# 20W-IR-Blaster_Simplified.net
KiCad netlist of a schematic drawn in EAGLE
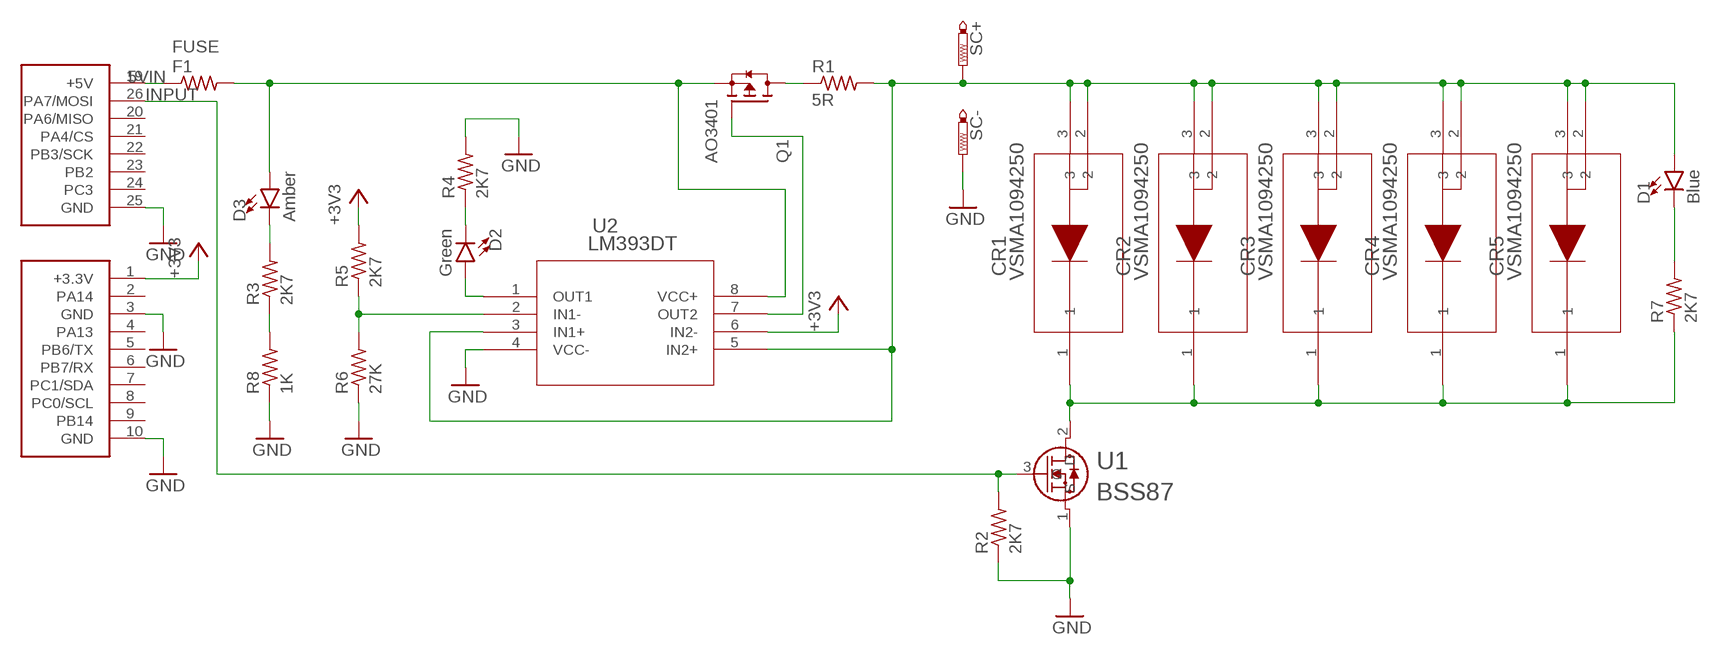
[diagram p0: schematic, sheet 1]

(export (version "E")
  (design (tool "Eeschema 10.0.6"))
  (components
    (comp (ref "CR1")
      (value "VSMA1094250")
      (footprint "eagle-import:DIODE_VSMA1094250_VIS")
      (fields (field (name "COPYRIGHT") "Copyright (C) 2025 Ultra Librarian. All rights reserved."))
      (libsource (lib "eagle-import") (part "VSMA1094250"))
    )
    (comp (ref "CR2")
      (value "VSMA1094250")
      (footprint "eagle-import:DIODE_VSMA1094250_VIS")
      (fields (field (name "COPYRIGHT") "Copyright (C) 2025 Ultra Librarian. All rights reserved."))
      (libsource (lib "eagle-import") (part "VSMA1094250"))
    )
    (comp (ref "CR3")
      (value "VSMA1094250")
      (footprint "eagle-import:DIODE_VSMA1094250_VIS")
      (fields (field (name "COPYRIGHT") "Copyright (C) 2025 Ultra Librarian. All rights reserved."))
      (libsource (lib "eagle-import") (part "VSMA1094250"))
    )
    (comp (ref "CR4")
      (value "VSMA1094250")
      (footprint "eagle-import:DIODE_VSMA1094250_VIS")
      (fields (field (name "COPYRIGHT") "Copyright (C) 2025 Ultra Librarian. All rights reserved."))
      (libsource (lib "eagle-import") (part "VSMA1094250"))
    )
    (comp (ref "CR5")
      (value "VSMA1094250")
      (footprint "eagle-import:DIODE_VSMA1094250_VIS")
      (fields (field (name "COPYRIGHT") "Copyright (C) 2025 Ultra Librarian. All rights reserved."))
      (libsource (lib "eagle-import") (part "VSMA1094250"))
    )
    (comp (ref "D1")
      (value "Blue")
      (footprint "eagle-import:LED-1206")
      (libsource (lib "eagle-import") (part "LED-BLUE1206"))
    )
    (comp (ref "D2")
      (value "Green")
      (footprint "eagle-import:LED-1206")
      (libsource (lib "eagle-import") (part "LED-GREEN1206"))
    )
    (comp (ref "D3")
      (value "Amber")
      (footprint "eagle-import:LED-1206")
      (libsource (lib "eagle-import") (part "LED-RED1206"))
    )
    (comp (ref "F1")
      (value "FUSE")
      (footprint "eagle-import:R1206")
      (libsource (lib "eagle-import") (part "R-US_R1206"))
    )
    (comp (ref "Q1")
      (value "AO3401")
      (footprint "eagle-import:AO3401")
      (fields (field (name "MANUFACTURER") "Diodes Inc."))
      (libsource (lib "eagle-import") (part "AO3401"))
    )
    (comp (ref "R1")
      (value "5R")
      (footprint "eagle-import:R2512")
      (libsource (lib "eagle-import") (part "R-US_R2512"))
    )
    (comp (ref "R2")
      (value "2K7")
      (footprint "eagle-import:R0805")
      (libsource (lib "eagle-import") (part "R-US_R0805"))
    )
    (comp (ref "R3")
      (value "2K7")
      (footprint "eagle-import:R0805")
      (libsource (lib "eagle-import") (part "R-US_R0805"))
    )
    (comp (ref "R4")
      (value "2K7")
      (footprint "eagle-import:R0805")
      (libsource (lib "eagle-import") (part "R-US_R0805"))
    )
    (comp (ref "R5")
      (value "2K7")
      (footprint "eagle-import:R0805")
      (libsource (lib "eagle-import") (part "R-US_R0805"))
    )
    (comp (ref "R6")
      (value "27K")
      (footprint "eagle-import:R0805")
      (libsource (lib "eagle-import") (part "R-US_R0805"))
    )
    (comp (ref "R7")
      (value "2K7")
      (footprint "eagle-import:R0805")
      (libsource (lib "eagle-import") (part "R-US_R0805"))
    )
    (comp (ref "R8")
      (value "1K")
      (footprint "eagle-import:R0805")
      (libsource (lib "eagle-import") (part "R-US_R0805"))
    )
    (comp (ref "SC+")
      (value "PTR1PAD1-20Y")
      (footprint "eagle-import:P1-20Y")
      (libsource (lib "eagle-import") (part "PTR1PAD1-20Y"))
    )
    (comp (ref "SC-")
      (value "PTR1PAD1-20Y")
      (footprint "eagle-import:P1-20Y")
      (libsource (lib "eagle-import") (part "PTR1PAD1-20Y"))
    )
    (comp (ref "U$1")
      (value "BOTH-SMD")
      (footprint "eagle-import:BOTH-SMD")
      (libsource (lib "eagle-import") (part "BOTH-SMD"))
    )
    (comp (ref "U1")
      (value "BSS87")
      (footprint "eagle-import:SOT89_NXP")
      (fields (field (name "COPYRIGHT") "Copyright (C) 2025 Ultra Librarian. All rights reserved."))
      (libsource (lib "eagle-import") (part "BSS87"))
    )
    (comp (ref "U2")
      (value "LM393DT")
      (footprint "eagle-import:SO8_STM")
      (fields (field (name "COPYRIGHT") "Copyright (C) 2025 Ultra Librarian. All rights reserved."))
      (libsource (lib "eagle-import") (part "LM393DT"))
    )
  )
  (nets
    (net (code "1") (name "+3V3") (class "Default")
      (node (ref "R5") (pin "2") (pinfunction "2_2") (pintype "passive"))
      (node (ref "U$1") (pin "1") (pinfunction "+3.3V_1") (pintype "bidirectional"))
      (node (ref "U2") (pin "6") (pinfunction "IN2-_6") (pintype "input"))
    )
    (net (code "2") (name "/5VIN") (class "Default")
      (node (ref "F1") (pin "1") (pinfunction "1_1") (pintype "passive"))
      (node (ref "U$1") (pin "19") (pinfunction "+5V_19") (pintype "bidirectional"))
    )
    (net (code "3") (name "/INPUT") (class "Default")
      (node (ref "R2") (pin "2") (pinfunction "2_2") (pintype "passive"))
      (node (ref "U$1") (pin "26") (pinfunction "PA7/MOSI_26") (pintype "bidirectional"))
      (node (ref "U1") (pin "3") (pinfunction "G_3") (pintype "passive"))
    )
    (net (code "4") (name "GND") (class "Default")
      (node (ref "R2") (pin "1") (pinfunction "1_1") (pintype "passive"))
      (node (ref "R4") (pin "2") (pinfunction "2_2") (pintype "passive"))
      (node (ref "R6") (pin "1") (pinfunction "1_1") (pintype "passive"))
      (node (ref "R8") (pin "1") (pinfunction "1_1") (pintype "passive"))
      (node (ref "SC-") (pin "TP") (pinfunction "TP_TP") (pintype "input"))
      (node (ref "U$1") (pin "10") (pinfunction "GND_10") (pintype "bidirectional"))
      (node (ref "U$1") (pin "25") (pinfunction "GND_25") (pintype "bidirectional"))
      (node (ref "U$1") (pin "3") (pinfunction "GND_3") (pintype "bidirectional"))
      (node (ref "U1") (pin "1") (pinfunction "S_1") (pintype "passive"))
      (node (ref "U2") (pin "4") (pinfunction "VCC-_4") (pintype "power_in"))
    )
    (net (code "5") (name "Net-(D1-PadC)") (class "Default")
      (node (ref "D1") (pin "C") (pinfunction "C_C") (pintype "passive"))
      (node (ref "R7") (pin "2") (pinfunction "2_2") (pintype "passive"))
    )
    (net (code "6") (name "Net-(D2-PadC)") (class "Default")
      (node (ref "D2") (pin "C") (pinfunction "C_C") (pintype "passive"))
      (node (ref "R4") (pin "1") (pinfunction "1_1") (pintype "passive"))
    )
    (net (code "7") (name "Net-(D3-PadC)") (class "Default")
      (node (ref "D3") (pin "C") (pinfunction "C_C") (pintype "passive"))
      (node (ref "R3") (pin "2") (pinfunction "2_2") (pintype "passive"))
    )
    (net (code "8") (name "Net-(Q1-D)") (class "Default")
      (node (ref "Q1") (pin "3") (pinfunction "D_3") (pintype "passive"))
      (node (ref "R1") (pin "1") (pinfunction "1_1") (pintype "passive"))
    )
    (net (code "9") (name "Net-(Q1-G)") (class "Default")
      (node (ref "Q1") (pin "1") (pinfunction "G_1") (pintype "passive"))
      (node (ref "U2") (pin "7") (pinfunction "OUT2_7") (pintype "output"))
    )
    (net (code "10") (name "Net-(Q1-S)") (class "Default")
      (node (ref "D3") (pin "A") (pinfunction "A_A") (pintype "passive"))
      (node (ref "F1") (pin "2") (pinfunction "2_2") (pintype "passive"))
      (node (ref "Q1") (pin "2") (pinfunction "S_2") (pintype "passive"))
      (node (ref "U2") (pin "8") (pinfunction "VCC+_8") (pintype "power_in"))
    )
    (net (code "11") (name "Net-(R3-Pad1)") (class "Default")
      (node (ref "R3") (pin "1") (pinfunction "1_1") (pintype "passive"))
      (node (ref "R8") (pin "2") (pinfunction "2_2") (pintype "passive"))
    )
    (net (code "12") (name "Net-(U1-D)") (class "Default")
      (node (ref "CR1") (pin "1") (pinfunction "1_1") (pintype "passive"))
      (node (ref "CR2") (pin "1") (pinfunction "1_1") (pintype "passive"))
      (node (ref "CR3") (pin "1") (pinfunction "1_1") (pintype "passive"))
      (node (ref "CR4") (pin "1") (pinfunction "1_1") (pintype "passive"))
      (node (ref "CR5") (pin "1") (pinfunction "1_1") (pintype "passive"))
      (node (ref "R7") (pin "1") (pinfunction "1_1") (pintype "passive"))
      (node (ref "U1") (pin "2") (pinfunction "D_2") (pintype "passive"))
    )
    (net (code "13") (name "Net-(U2-IN1+)") (class "Default")
      (node (ref "CR1") (pin "2") (pinfunction "2_2") (pintype "passive"))
      (node (ref "CR1") (pin "3") (pinfunction "3_3") (pintype "passive"))
      (node (ref "CR2") (pin "2") (pinfunction "2_2") (pintype "passive"))
      (node (ref "CR2") (pin "3") (pinfunction "3_3") (pintype "passive"))
      (node (ref "CR3") (pin "2") (pinfunction "2_2") (pintype "passive"))
      (node (ref "CR3") (pin "3") (pinfunction "3_3") (pintype "passive"))
      (node (ref "CR4") (pin "2") (pinfunction "2_2") (pintype "passive"))
      (node (ref "CR4") (pin "3") (pinfunction "3_3") (pintype "passive"))
      (node (ref "CR5") (pin "2") (pinfunction "2_2") (pintype "passive"))
      (node (ref "CR5") (pin "3") (pinfunction "3_3") (pintype "passive"))
      (node (ref "D1") (pin "A") (pinfunction "A_A") (pintype "passive"))
      (node (ref "R1") (pin "2") (pinfunction "2_2") (pintype "passive"))
      (node (ref "SC+") (pin "TP") (pinfunction "TP_TP") (pintype "input"))
      (node (ref "U2") (pin "3") (pinfunction "IN1+_3") (pintype "input"))
      (node (ref "U2") (pin "5") (pinfunction "IN2+_5") (pintype "input"))
    )
    (net (code "14") (name "Net-(U2-IN1-)") (class "Default")
      (node (ref "R5") (pin "1") (pinfunction "1_1") (pintype "passive"))
      (node (ref "R6") (pin "2") (pinfunction "2_2") (pintype "passive"))
      (node (ref "U2") (pin "2") (pinfunction "IN1-_2") (pintype "input"))
    )
    (net (code "15") (name "Net-(U2-OUT1)") (class "Default")
      (node (ref "D2") (pin "A") (pinfunction "A_A") (pintype "passive"))
      (node (ref "U2") (pin "1") (pinfunction "OUT1_1") (pintype "output"))
    )
    (net (code "16") (name "unconnected-(U$1A-PA4{slash}CS-Pad21)") (class "Default")
      (node (ref "U$1") (pin "21") (pinfunction "PA4/CS_21") (pintype "bidirectional"))
    )
    (net (code "17") (name "unconnected-(U$1A-PA6{slash}MISO-Pad20)") (class "Default")
      (node (ref "U$1") (pin "20") (pinfunction "PA6/MISO_20") (pintype "bidirectional"))
    )
    (net (code "18") (name "unconnected-(U$1A-PB2-Pad23)") (class "Default")
      (node (ref "U$1") (pin "23") (pinfunction "PB2_23") (pintype "bidirectional"))
    )
    (net (code "19") (name "unconnected-(U$1A-PB3{slash}SCK-Pad22)") (class "Default")
      (node (ref "U$1") (pin "22") (pinfunction "PB3/SCK_22") (pintype "bidirectional"))
    )
    (net (code "20") (name "unconnected-(U$1A-PC3-Pad24)") (class "Default")
      (node (ref "U$1") (pin "24") (pinfunction "PC3_24") (pintype "bidirectional"))
    )
    (net (code "21") (name "unconnected-(U$1B-PA13-Pad4)") (class "Default")
      (node (ref "U$1") (pin "4") (pinfunction "PA13_4") (pintype "bidirectional"))
    )
    (net (code "22") (name "unconnected-(U$1B-PA14-Pad2)") (class "Default")
      (node (ref "U$1") (pin "2") (pinfunction "PA14_2") (pintype "bidirectional"))
    )
    (net (code "23") (name "unconnected-(U$1B-PB6{slash}TX-Pad5)") (class "Default")
      (node (ref "U$1") (pin "5") (pinfunction "PB6/TX_5") (pintype "bidirectional"))
    )
    (net (code "24") (name "unconnected-(U$1B-PB7{slash}RX-Pad6)") (class "Default")
      (node (ref "U$1") (pin "6") (pinfunction "PB7/RX_6") (pintype "bidirectional"))
    )
    (net (code "25") (name "unconnected-(U$1B-PB14-Pad9)") (class "Default")
      (node (ref "U$1") (pin "9") (pinfunction "PB14_9") (pintype "bidirectional"))
    )
    (net (code "26") (name "unconnected-(U$1B-PC0{slash}SCL-Pad8)") (class "Default")
      (node (ref "U$1") (pin "8") (pinfunction "PC0/SCL_8") (pintype "bidirectional"))
    )
    (net (code "27") (name "unconnected-(U$1B-PC1{slash}SDA-Pad7)") (class "Default")
      (node (ref "U$1") (pin "7") (pinfunction "PC1/SDA_7") (pintype "bidirectional"))
    )
  )
)
